# 11_RK3568_DDR_PHY.net
KiCad netlist of a schematic drawn in Altium Designer
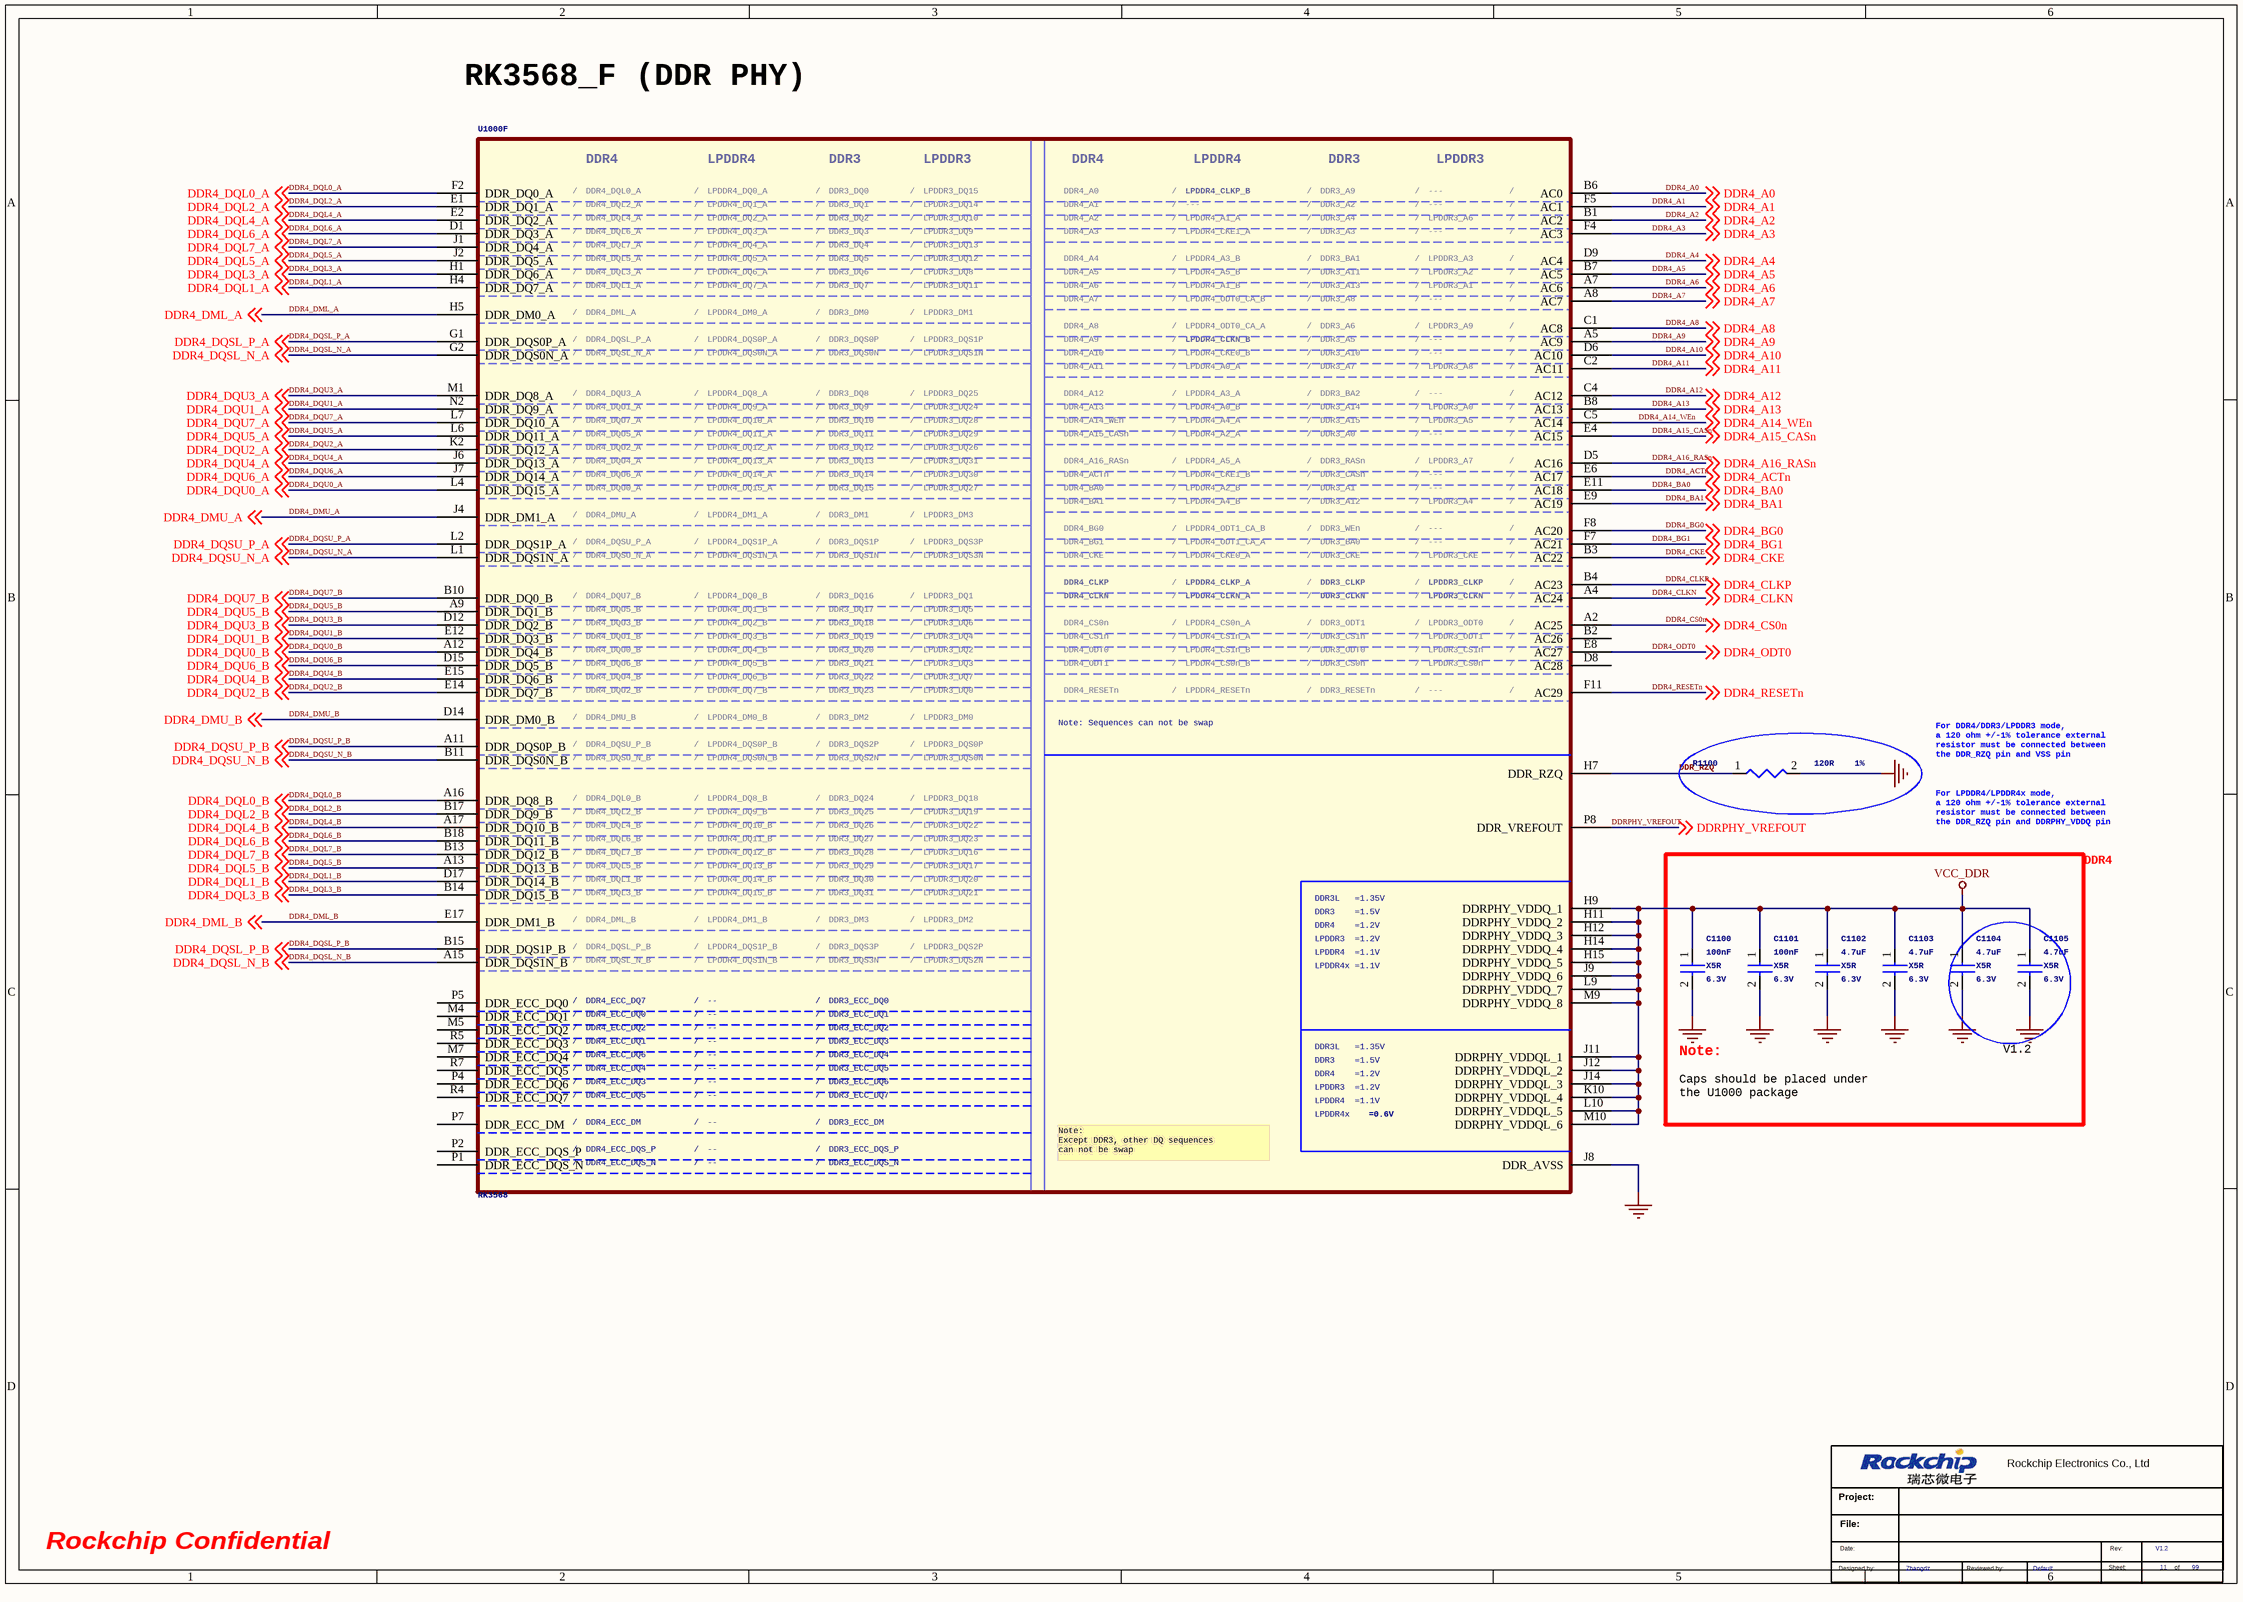
[diagram p0: 11.RK3568_DDR PHY.SchDoc]

(export (version "E")
  (design (tool "Eeschema 10.0.6"))
  (components
    (comp (ref "*")
      (value "Rockchip_new")
      (fields
        (field (name "SCHEMATIC PAGE COUNT") "99")
        (field (name "SCHEMATIC PAGE NUMBER") "11")
        (field (name "DESIGNER") "Zhangdz")
        (field (name "REVISION") "V1.2")
        (field (name "CHECK") "Default")
      )
      (libsource (lib "*") (part "Rockchip_new"))
    )
    (comp (ref "C1100")
      (value "100nF")
      (footprint "C0201")
      (description "cap,100.00nF,+/-10%,6.3V,X5R,C0201")
      (fields
        (field (name "VOLTAGE") "6.3V")
        (field (name "DIELECTRIC") "X5R")
        (field (name "MANUFACTURER") "TDK")
        (field (name "TOLERANCE") "10%")
        (field (name "CREATED BY") "JJJ")
      )
      (libsource (lib "*") (part "CAP NP"))
    )
    (comp (ref "C1101")
      (value "100nF")
      (footprint "C0201")
      (description "cap,100.00nF,+/-10%,6.3V,X5R,C0201")
      (fields
        (field (name "VOLTAGE") "6.3V")
        (field (name "DIELECTRIC") "X5R")
        (field (name "MANUFACTURER") "TDK")
        (field (name "TOLERANCE") "10%")
        (field (name "CREATED BY") "JJJ")
      )
      (libsource (lib "*") (part "CAP NP"))
    )
    (comp (ref "C1102")
      (value "4.7uF")
      (footprint "C0402")
      (description "cap,4.70uF,+/-10%,6.3V,X5R,C0402")
      (fields
        (field (name "VOLTAGE") "6.3V")
        (field (name "DIELECTRIC") "X5R")
        (field (name "TOLERANCE") "10%")
        (field (name "MANUFACTURER") "TDK")
        (field (name "CREATED BY") "JJJ")
      )
      (libsource (lib "*") (part "CAP NP"))
    )
    (comp (ref "C1103")
      (value "4.7uF")
      (footprint "C0402")
      (description "cap,4.70uF,+/-10%,6.3V,X5R,C0402")
      (fields
        (field (name "VOLTAGE") "6.3V")
        (field (name "DIELECTRIC") "X5R")
        (field (name "MANUFACTURER") "TDK")
        (field (name "TOLERANCE") "10%")
        (field (name "CREATED BY") "JJJ")
      )
      (libsource (lib "*") (part "CAP NP"))
    )
    (comp (ref "C1104")
      (value "4.7uF")
      (footprint "C0402")
      (description "cap,4.70uF,+/-10%,6.3V,X5R,C0402")
      (fields
        (field (name "VOLTAGE") "6.3V")
        (field (name "DIELECTRIC") "X5R")
        (field (name "TOLERANCE") "10%")
        (field (name "MANUFACTURER") "TDK")
        (field (name "CREATED BY") "JJJ")
      )
      (libsource (lib "*") (part "CAP NP"))
    )
    (comp (ref "C1105")
      (value "4.7uF")
      (footprint "C0402")
      (description "cap,4.70uF,+/-10%,6.3V,X5R,C0402")
      (fields
        (field (name "VOLTAGE") "6.3V")
        (field (name "DIELECTRIC") "X5R")
        (field (name "TOLERANCE") "10%")
        (field (name "MANUFACTURER") "TDK")
        (field (name "CREATED BY") "JJJ")
      )
      (libsource (lib "*") (part "CAP NP"))
    )
    (comp (ref "R1100")
      (value "120R")
      (footprint "R0201")
      (description "通用厚膜电阻,120R,+/-1%,R0201,1/20W.")
      (fields
        (field (name "TOLERANCE") "1%")
        (field (name "MANUFACTURER") "YAGEO")
        (field (name "CREATED BY") "YTL")
      )
      (libsource (lib "*") (part "RESISTOR"))
    )
    (comp (ref "U1000")
      (value "RK3568")
      (footprint "BGA636_19R00X19R00X1R20")
      (description "ROCKCHIP SOC")
      (fields (field (name "MANUFACTURER") "Rockchip (瑞芯微)") (field (name "CREATED BY") "JJJ"))
      (libsource (lib "*") (part "SOC_RK3568"))
    )
  )
  (nets
    (net (code "1") (name "/DDR_RZQ") (class "Default")
      (node (ref "R1100") (pin "1") (pinfunction "1_1") (pintype "passive"))
      (node (ref "U1000") (pin "H7") (pinfunction "DDR_RZQ_H7") (pintype "passive"))
    )
    (net (code "2") (name "DDR4_A0") (class "Default")
      (node (ref "U1000") (pin "B6") (pinfunction "AC0_B6") (pintype "passive"))
    )
    (net (code "3") (name "DDR4_A1") (class "Default")
      (node (ref "U1000") (pin "F5") (pinfunction "AC1_F5") (pintype "passive"))
    )
    (net (code "4") (name "DDR4_A2") (class "Default")
      (node (ref "U1000") (pin "B1") (pinfunction "AC2_B1") (pintype "passive"))
    )
    (net (code "5") (name "DDR4_A3") (class "Default")
      (node (ref "U1000") (pin "F4") (pinfunction "AC3_F4") (pintype "passive"))
    )
    (net (code "6") (name "DDR4_A4") (class "Default")
      (node (ref "U1000") (pin "D9") (pinfunction "AC4_D9") (pintype "passive"))
    )
    (net (code "7") (name "DDR4_A5") (class "Default")
      (node (ref "U1000") (pin "B7") (pinfunction "AC5_B7") (pintype "passive"))
    )
    (net (code "8") (name "DDR4_A6") (class "Default")
      (node (ref "U1000") (pin "A7") (pinfunction "AC6_A7") (pintype "passive"))
    )
    (net (code "9") (name "DDR4_A7") (class "Default")
      (node (ref "U1000") (pin "A8") (pinfunction "AC7_A8") (pintype "passive"))
    )
    (net (code "10") (name "DDR4_A8") (class "Default")
      (node (ref "U1000") (pin "C1") (pinfunction "AC8_C1") (pintype "passive"))
    )
    (net (code "11") (name "DDR4_A9") (class "Default")
      (node (ref "U1000") (pin "A5") (pinfunction "AC9_A5") (pintype "passive"))
    )
    (net (code "12") (name "DDR4_A10") (class "Default")
      (node (ref "U1000") (pin "D6") (pinfunction "AC10_D6") (pintype "passive"))
    )
    (net (code "13") (name "DDR4_A11") (class "Default")
      (node (ref "U1000") (pin "C2") (pinfunction "AC11_C2") (pintype "passive"))
    )
    (net (code "14") (name "DDR4_A12") (class "Default")
      (node (ref "U1000") (pin "C4") (pinfunction "AC12_C4") (pintype "passive"))
    )
    (net (code "15") (name "DDR4_A13") (class "Default")
      (node (ref "U1000") (pin "B8") (pinfunction "AC13_B8") (pintype "passive"))
    )
    (net (code "16") (name "DDR4_A14_WEn") (class "Default")
      (node (ref "U1000") (pin "C5") (pinfunction "AC14_C5") (pintype "passive"))
    )
    (net (code "17") (name "DDR4_A15_CASn") (class "Default")
      (node (ref "U1000") (pin "E4") (pinfunction "AC15_E4") (pintype "passive"))
    )
    (net (code "18") (name "DDR4_A16_RASn") (class "Default")
      (node (ref "U1000") (pin "D5") (pinfunction "AC16_D5") (pintype "passive"))
    )
    (net (code "19") (name "DDR4_ACTn") (class "Default")
      (node (ref "U1000") (pin "E6") (pinfunction "AC17_E6") (pintype "passive"))
    )
    (net (code "20") (name "DDR4_BA0") (class "Default")
      (node (ref "U1000") (pin "E11") (pinfunction "AC18_E11") (pintype "passive"))
    )
    (net (code "21") (name "DDR4_BA1") (class "Default")
      (node (ref "U1000") (pin "E9") (pinfunction "AC19_E9") (pintype "passive"))
    )
    (net (code "22") (name "DDR4_BG0") (class "Default")
      (node (ref "U1000") (pin "F8") (pinfunction "AC20_F8") (pintype "passive"))
    )
    (net (code "23") (name "DDR4_BG1") (class "Default")
      (node (ref "U1000") (pin "F7") (pinfunction "AC21_F7") (pintype "passive"))
    )
    (net (code "24") (name "DDR4_CKE") (class "Default")
      (node (ref "U1000") (pin "B3") (pinfunction "AC22_B3") (pintype "passive"))
    )
    (net (code "25") (name "DDR4_CLKN") (class "Default")
      (node (ref "U1000") (pin "A4") (pinfunction "AC24_A4") (pintype "passive"))
    )
    (net (code "26") (name "DDR4_CLKP") (class "Default")
      (node (ref "U1000") (pin "B4") (pinfunction "AC23_B4") (pintype "passive"))
    )
    (net (code "27") (name "DDR4_CS0n") (class "Default")
      (node (ref "U1000") (pin "A2") (pinfunction "AC25_A2") (pintype "passive"))
    )
    (net (code "28") (name "DDR4_DML_A") (class "Default")
      (node (ref "U1000") (pin "H5") (pinfunction "DDR_DM0_A_H5") (pintype "passive"))
    )
    (net (code "29") (name "DDR4_DML_B") (class "Default")
      (node (ref "U1000") (pin "E17") (pinfunction "DDR_DM1_B_E17") (pintype "passive"))
    )
    (net (code "30") (name "DDR4_DMU_A") (class "Default")
      (node (ref "U1000") (pin "J4") (pinfunction "DDR_DM1_A_J4") (pintype "passive"))
    )
    (net (code "31") (name "DDR4_DMU_B") (class "Default")
      (node (ref "U1000") (pin "D14") (pinfunction "DDR_DM0_B_D14") (pintype "passive"))
    )
    (net (code "32") (name "DDR4_DQL0_A") (class "Default")
      (node (ref "U1000") (pin "F2") (pinfunction "DDR_DQ0_A_F2") (pintype "passive"))
    )
    (net (code "33") (name "DDR4_DQL0_B") (class "Default")
      (node (ref "U1000") (pin "A16") (pinfunction "DDR_DQ8_B_A16") (pintype "passive"))
    )
    (net (code "34") (name "DDR4_DQL1_A") (class "Default")
      (node (ref "U1000") (pin "H4") (pinfunction "DDR_DQ7_A_H4") (pintype "passive"))
    )
    (net (code "35") (name "DDR4_DQL1_B") (class "Default")
      (node (ref "U1000") (pin "D17") (pinfunction "DDR_DQ14_B_D17") (pintype "passive"))
    )
    (net (code "36") (name "DDR4_DQL2_A") (class "Default")
      (node (ref "U1000") (pin "E1") (pinfunction "DDR_DQ1_A_E1") (pintype "passive"))
    )
    (net (code "37") (name "DDR4_DQL2_B") (class "Default")
      (node (ref "U1000") (pin "B17") (pinfunction "DDR_DQ9_B_B17") (pintype "passive"))
    )
    (net (code "38") (name "DDR4_DQL3_A") (class "Default")
      (node (ref "U1000") (pin "H1") (pinfunction "DDR_DQ6_A_H1") (pintype "passive"))
    )
    (net (code "39") (name "DDR4_DQL3_B") (class "Default")
      (node (ref "U1000") (pin "B14") (pinfunction "DDR_DQ15_B_B14") (pintype "passive"))
    )
    (net (code "40") (name "DDR4_DQL4_A") (class "Default")
      (node (ref "U1000") (pin "E2") (pinfunction "DDR_DQ2_A_E2") (pintype "passive"))
    )
    (net (code "41") (name "DDR4_DQL4_B") (class "Default")
      (node (ref "U1000") (pin "A17") (pinfunction "DDR_DQ10_B_A17") (pintype "passive"))
    )
    (net (code "42") (name "DDR4_DQL5_A") (class "Default")
      (node (ref "U1000") (pin "J2") (pinfunction "DDR_DQ5_A_J2") (pintype "passive"))
    )
    (net (code "43") (name "DDR4_DQL5_B") (class "Default")
      (node (ref "U1000") (pin "A13") (pinfunction "DDR_DQ13_B_A13") (pintype "passive"))
    )
    (net (code "44") (name "DDR4_DQL6_A") (class "Default")
      (node (ref "U1000") (pin "D1") (pinfunction "DDR_DQ3_A_D1") (pintype "passive"))
    )
    (net (code "45") (name "DDR4_DQL6_B") (class "Default")
      (node (ref "U1000") (pin "B18") (pinfunction "DDR_DQ11_B_B18") (pintype "passive"))
    )
    (net (code "46") (name "DDR4_DQL7_A") (class "Default")
      (node (ref "U1000") (pin "J1") (pinfunction "DDR_DQ4_A_J1") (pintype "passive"))
    )
    (net (code "47") (name "DDR4_DQL7_B") (class "Default")
      (node (ref "U1000") (pin "B13") (pinfunction "DDR_DQ12_B_B13") (pintype "passive"))
    )
    (net (code "48") (name "DDR4_DQSL_N_A") (class "Default")
      (node (ref "U1000") (pin "G2") (pinfunction "DDR_DQS0N_A_G2") (pintype "passive"))
    )
    (net (code "49") (name "DDR4_DQSL_N_B") (class "Default")
      (node (ref "U1000") (pin "A15") (pinfunction "DDR_DQS1N_B_A15") (pintype "passive"))
    )
    (net (code "50") (name "DDR4_DQSL_P_A") (class "Default")
      (node (ref "U1000") (pin "G1") (pinfunction "DDR_DQS0P_A_G1") (pintype "passive"))
    )
    (net (code "51") (name "DDR4_DQSL_P_B") (class "Default")
      (node (ref "U1000") (pin "B15") (pinfunction "DDR_DQS1P_B_B15") (pintype "passive"))
    )
    (net (code "52") (name "DDR4_DQSU_N_A") (class "Default")
      (node (ref "U1000") (pin "L1") (pinfunction "DDR_DQS1N_A_L1") (pintype "passive"))
    )
    (net (code "53") (name "DDR4_DQSU_N_B") (class "Default")
      (node (ref "U1000") (pin "B11") (pinfunction "DDR_DQS0N_B_B11") (pintype "passive"))
    )
    (net (code "54") (name "DDR4_DQSU_P_A") (class "Default")
      (node (ref "U1000") (pin "L2") (pinfunction "DDR_DQS1P_A_L2") (pintype "passive"))
    )
    (net (code "55") (name "DDR4_DQSU_P_B") (class "Default")
      (node (ref "U1000") (pin "A11") (pinfunction "DDR_DQS0P_B_A11") (pintype "passive"))
    )
    (net (code "56") (name "DDR4_DQU0_A") (class "Default")
      (node (ref "U1000") (pin "L4") (pinfunction "DDR_DQ15_A_L4") (pintype "passive"))
    )
    (net (code "57") (name "DDR4_DQU0_B") (class "Default")
      (node (ref "U1000") (pin "A12") (pinfunction "DDR_DQ4_B_A12") (pintype "passive"))
    )
    (net (code "58") (name "DDR4_DQU1_A") (class "Default")
      (node (ref "U1000") (pin "N2") (pinfunction "DDR_DQ9_A_N2") (pintype "passive"))
    )
    (net (code "59") (name "DDR4_DQU1_B") (class "Default")
      (node (ref "U1000") (pin "E12") (pinfunction "DDR_DQ3_B_E12") (pintype "passive"))
    )
    (net (code "60") (name "DDR4_DQU2_A") (class "Default")
      (node (ref "U1000") (pin "K2") (pinfunction "DDR_DQ12_A_K2") (pintype "passive"))
    )
    (net (code "61") (name "DDR4_DQU2_B") (class "Default")
      (node (ref "U1000") (pin "E14") (pinfunction "DDR_DQ7_B_E14") (pintype "passive"))
    )
    (net (code "62") (name "DDR4_DQU3_A") (class "Default")
      (node (ref "U1000") (pin "M1") (pinfunction "DDR_DQ8_A_M1") (pintype "passive"))
    )
    (net (code "63") (name "DDR4_DQU3_B") (class "Default")
      (node (ref "U1000") (pin "D12") (pinfunction "DDR_DQ2_B_D12") (pintype "passive"))
    )
    (net (code "64") (name "DDR4_DQU4_A") (class "Default")
      (node (ref "U1000") (pin "J6") (pinfunction "DDR_DQ13_A_J6") (pintype "passive"))
    )
    (net (code "65") (name "DDR4_DQU4_B") (class "Default")
      (node (ref "U1000") (pin "E15") (pinfunction "DDR_DQ6_B_E15") (pintype "passive"))
    )
    (net (code "66") (name "DDR4_DQU5_A") (class "Default")
      (node (ref "U1000") (pin "L6") (pinfunction "DDR_DQ11_A_L6") (pintype "passive"))
    )
    (net (code "67") (name "DDR4_DQU5_B") (class "Default")
      (node (ref "U1000") (pin "A9") (pinfunction "DDR_DQ1_B_A9") (pintype "passive"))
    )
    (net (code "68") (name "DDR4_DQU6_A") (class "Default")
      (node (ref "U1000") (pin "J7") (pinfunction "DDR_DQ14_A_J7") (pintype "passive"))
    )
    (net (code "69") (name "DDR4_DQU6_B") (class "Default")
      (node (ref "U1000") (pin "D15") (pinfunction "DDR_DQ5_B_D15") (pintype "passive"))
    )
    (net (code "70") (name "DDR4_DQU7_A") (class "Default")
      (node (ref "U1000") (pin "L7") (pinfunction "DDR_DQ10_A_L7") (pintype "passive"))
    )
    (net (code "71") (name "DDR4_DQU7_B") (class "Default")
      (node (ref "U1000") (pin "B10") (pinfunction "DDR_DQ0_B_B10") (pintype "passive"))
    )
    (net (code "72") (name "DDR4_ODT0") (class "Default")
      (node (ref "U1000") (pin "E8") (pinfunction "AC27_E8") (pintype "passive"))
    )
    (net (code "73") (name "DDR4_RESETn") (class "Default")
      (node (ref "U1000") (pin "F11") (pinfunction "AC29_F11") (pintype "passive"))
    )
    (net (code "74") (name "DDRPHY_VREFOUT") (class "Default")
      (node (ref "U1000") (pin "P8") (pinfunction "DDR_VREFOUT_P8") (pintype "passive"))
    )
    (net (code "75") (name "GND") (class "Default")
      (node (ref "C1100") (pin "2") (pinfunction "2_2") (pintype "passive"))
      (node (ref "C1101") (pin "2") (pinfunction "2_2") (pintype "passive"))
      (node (ref "C1102") (pin "2") (pinfunction "2_2") (pintype "passive"))
      (node (ref "C1103") (pin "2") (pinfunction "2_2") (pintype "passive"))
      (node (ref "C1104") (pin "2") (pinfunction "2_2") (pintype "passive"))
      (node (ref "C1105") (pin "2") (pinfunction "2_2") (pintype "passive"))
      (node (ref "R1100") (pin "2") (pinfunction "2_2") (pintype "passive"))
      (node (ref "U1000") (pin "J8") (pinfunction "DDR_AVSS_J8") (pintype "passive"))
    )
    (net (code "76") (name "VCC_DDR") (class "Default")
      (node (ref "C1100") (pin "1") (pinfunction "1_1") (pintype "passive"))
      (node (ref "C1101") (pin "1") (pinfunction "1_1") (pintype "passive"))
      (node (ref "C1102") (pin "1") (pinfunction "1_1") (pintype "passive"))
      (node (ref "C1103") (pin "1") (pinfunction "1_1") (pintype "passive"))
      (node (ref "C1104") (pin "1") (pinfunction "1_1") (pintype "passive"))
      (node (ref "C1105") (pin "1") (pinfunction "1_1") (pintype "passive"))
      (node (ref "U1000") (pin "H11") (pinfunction "DDRPHY_VDDQ_2_H11") (pintype "passive"))
      (node (ref "U1000") (pin "H12") (pinfunction "DDRPHY_VDDQ_3_H12") (pintype "passive"))
      (node (ref "U1000") (pin "H14") (pinfunction "DDRPHY_VDDQ_4_H14") (pintype "passive"))
      (node (ref "U1000") (pin "H15") (pinfunction "DDRPHY_VDDQ_5_H15") (pintype "passive"))
      (node (ref "U1000") (pin "H9") (pinfunction "DDRPHY_VDDQ_1_H9") (pintype "passive"))
      (node (ref "U1000") (pin "J11") (pinfunction "DDRPHY_VDDQL_1_J11") (pintype "passive"))
      (node (ref "U1000") (pin "J12") (pinfunction "DDRPHY_VDDQL_2_J12") (pintype "passive"))
      (node (ref "U1000") (pin "J14") (pinfunction "DDRPHY_VDDQL_3_J14") (pintype "passive"))
      (node (ref "U1000") (pin "J9") (pinfunction "DDRPHY_VDDQ_6_J9") (pintype "passive"))
      (node (ref "U1000") (pin "K10") (pinfunction "DDRPHY_VDDQL_4_K10") (pintype "passive"))
      (node (ref "U1000") (pin "L10") (pinfunction "DDRPHY_VDDQL_5_L10") (pintype "passive"))
      (node (ref "U1000") (pin "L9") (pinfunction "DDRPHY_VDDQ_7_L9") (pintype "passive"))
      (node (ref "U1000") (pin "M10") (pinfunction "DDRPHY_VDDQL_6_M10") (pintype "passive"))
      (node (ref "U1000") (pin "M9") (pinfunction "DDRPHY_VDDQ_8_M9") (pintype "passive"))
    )
    (net (code "77") (name "unconnected-(U1000F-AC26-PadB2)") (class "Default")
      (node (ref "U1000") (pin "B2") (pinfunction "AC26_B2") (pintype "passive"))
    )
    (net (code "78") (name "unconnected-(U1000F-AC28-PadD8)") (class "Default")
      (node (ref "U1000") (pin "D8") (pinfunction "AC28_D8") (pintype "passive"))
    )
    (net (code "79") (name "unconnected-(U1000F-DDR_ECC_DM-PadP7)") (class "Default")
      (node (ref "U1000") (pin "P7") (pinfunction "DDR_ECC_DM_P7") (pintype "passive"))
    )
    (net (code "80") (name "unconnected-(U1000F-DDR_ECC_DQ0-PadP5)") (class "Default")
      (node (ref "U1000") (pin "P5") (pinfunction "DDR_ECC_DQ0_P5") (pintype "passive"))
    )
    (net (code "81") (name "unconnected-(U1000F-DDR_ECC_DQ1-PadM4)") (class "Default")
      (node (ref "U1000") (pin "M4") (pinfunction "DDR_ECC_DQ1_M4") (pintype "passive"))
    )
    (net (code "82") (name "unconnected-(U1000F-DDR_ECC_DQ2-PadM5)") (class "Default")
      (node (ref "U1000") (pin "M5") (pinfunction "DDR_ECC_DQ2_M5") (pintype "passive"))
    )
    (net (code "83") (name "unconnected-(U1000F-DDR_ECC_DQ3-PadR5)") (class "Default")
      (node (ref "U1000") (pin "R5") (pinfunction "DDR_ECC_DQ3_R5") (pintype "passive"))
    )
    (net (code "84") (name "unconnected-(U1000F-DDR_ECC_DQ4-PadM7)") (class "Default")
      (node (ref "U1000") (pin "M7") (pinfunction "DDR_ECC_DQ4_M7") (pintype "passive"))
    )
    (net (code "85") (name "unconnected-(U1000F-DDR_ECC_DQ5-PadR7)") (class "Default")
      (node (ref "U1000") (pin "R7") (pinfunction "DDR_ECC_DQ5_R7") (pintype "passive"))
    )
    (net (code "86") (name "unconnected-(U1000F-DDR_ECC_DQ6-PadP4)") (class "Default")
      (node (ref "U1000") (pin "P4") (pinfunction "DDR_ECC_DQ6_P4") (pintype "passive"))
    )
    (net (code "87") (name "unconnected-(U1000F-DDR_ECC_DQ7-PadR4)") (class "Default")
      (node (ref "U1000") (pin "R4") (pinfunction "DDR_ECC_DQ7_R4") (pintype "passive"))
    )
    (net (code "88") (name "unconnected-(U1000F-DDR_ECC_DQS_N-PadP1)") (class "Default")
      (node (ref "U1000") (pin "P1") (pinfunction "DDR_ECC_DQS_N_P1") (pintype "passive"))
    )
    (net (code "89") (name "unconnected-(U1000F-DDR_ECC_DQS_P-PadP2)") (class "Default")
      (node (ref "U1000") (pin "P2") (pinfunction "DDR_ECC_DQS_P_P2") (pintype "passive"))
    )
  )
)
